# btn7960_board.net
KiCad netlist of a schematic drawn in Altium Designer
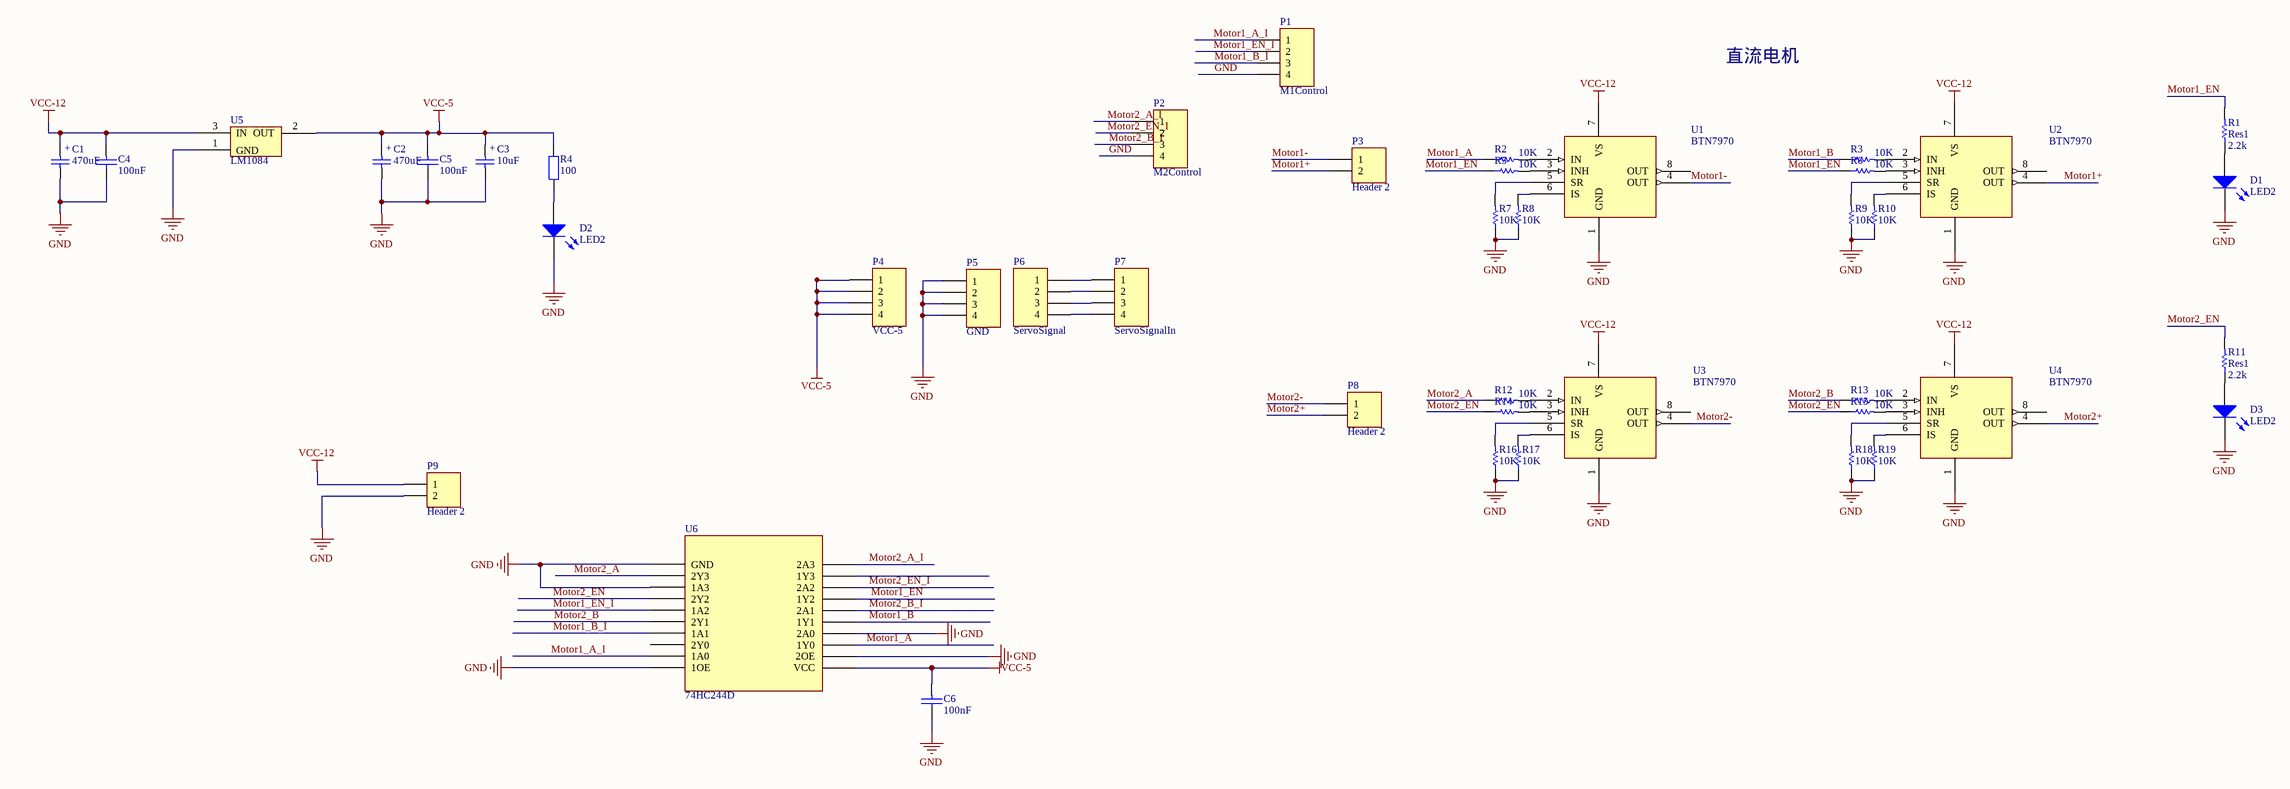
[diagram p0: btn7960_board.SchDoc]

(export (version "E")
  (design (tool "Eeschema 10.0.6"))
  (components
    (comp (ref "C1")
      (value "470uF")
      (footprint "CAP-7343")
      (description "贴片极性电容")
      (fields (field (name "Comment") "Cap"))
      (libsource (lib "SkyWorks2") (part "Cap Pol S"))
    )
    (comp (ref "C2")
      (value "470uF")
      (footprint "CAP-7343")
      (description "贴片极性电容")
      (fields (field (name "Comment") "Cap"))
      (libsource (lib "SkyWorks2") (part "Cap Pol S"))
    )
    (comp (ref "C3")
      (value "10uF")
      (footprint "CAP-7343")
      (description "贴片极性电容")
      (fields (field (name "Comment") "Cap"))
      (libsource (lib "SkyWorks2") (part "Cap Pol S"))
    )
    (comp (ref "C4")
      (value "100nF")
      (footprint "CAP-0603")
      (description "贴片无极性电容")
      (fields (field (name "Comment") "cap smd"))
      (libsource (lib "SkyWorks2") (part "CAP"))
    )
    (comp (ref "C5")
      (value "100nF")
      (footprint "CAP-0603")
      (description "贴片无极性电容")
      (fields (field (name "Comment") "cap smd"))
      (libsource (lib "SkyWorks2") (part "CAP"))
    )
    (comp (ref "C6")
      (value "100nF")
      (footprint "CAP-0603")
      (description "贴片无极性电容")
      (fields (field (name "Comment") "cap smd"))
      (libsource (lib "SkyWorks2") (part "CAP"))
    )
    (comp (ref "D1")
      (value "LED2")
      (footprint "D2012[0805]")
      (description "Typical RED, GREEN, YELLOW, AMBER GaAs LED")
      (fields (field (name "PUBLISHER") "Altium Limited"))
      (libsource (lib "Miscellaneous Devices") (part "LED2"))
    )
    (comp (ref "D2")
      (value "LED2")
      (footprint "D2012[0805]")
      (description "Typical RED, GREEN, YELLOW, AMBER GaAs LED")
      (fields (field (name "PUBLISHER") "Altium Limited"))
      (libsource (lib "SkyWorks2") (part "LED2"))
    )
    (comp (ref "D3")
      (value "LED2")
      (footprint "D2012[0805]")
      (description "Typical RED, GREEN, YELLOW, AMBER GaAs LED")
      (fields (field (name "PUBLISHER") "Altium Limited"))
      (libsource (lib "Miscellaneous Devices") (part "LED2"))
    )
    (comp (ref "P1")
      (value "M1Control")
      (footprint "HDR1X4")
      (description "Header, 4-Pin")
      (fields (field (name "PUBLISHER") "Altium Limited"))
      (libsource (lib "Miscellaneous Connectors") (part "Header 4"))
    )
    (comp (ref "P2")
      (value "M2Control")
      (footprint "HDR1X4")
      (description "Header, 4-Pin")
      (fields (field (name "PUBLISHER") "Altium Limited"))
      (libsource (lib "Miscellaneous Connectors") (part "Header 4"))
    )
    (comp (ref "P3")
      (value "Header 2")
      (footprint "WJ500V-5.08-2P")
      (description "Header, 2-Pin")
      (fields (field (name "PUBLISHER") "Altium Limited"))
      (libsource (lib "Miscellaneous Connectors") (part "Header 2"))
    )
    (comp (ref "P4")
      (value "VCC-5")
      (footprint "HDR1X4")
      (description "Header, 4-Pin")
      (fields (field (name "PUBLISHER") "Altium Limited"))
      (libsource (lib "Miscellaneous Connectors") (part "Header 4"))
    )
    (comp (ref "P5")
      (value "GND")
      (footprint "HDR1X4")
      (description "Header, 4-Pin")
      (fields (field (name "PUBLISHER") "Altium Limited"))
      (libsource (lib "Miscellaneous Connectors") (part "Header 4"))
    )
    (comp (ref "P6")
      (value "ServoSignal")
      (footprint "HDR1X4")
      (description "Header, 4-Pin")
      (fields (field (name "PUBLISHER") "Altium Limited"))
      (libsource (lib "") (part "Header 4_1"))
    )
    (comp (ref "P7")
      (value "ServoSignalIn")
      (footprint "HDR1X4")
      (description "Header, 4-Pin")
      (fields (field (name "PUBLISHER") "Altium Limited"))
      (libsource (lib "Miscellaneous Connectors") (part "Header 4"))
    )
    (comp (ref "P8")
      (value "Header 2")
      (footprint "WJ500V-5.08-2P")
      (description "Header, 2-Pin")
      (fields (field (name "PUBLISHER") "Altium Limited"))
      (libsource (lib "Miscellaneous Connectors") (part "Header 2"))
    )
    (comp (ref "P9")
      (value "Header 2")
      (footprint "WJ500V-5.08-2P")
      (description "Header, 2-Pin")
      (fields (field (name "PUBLISHER") "Altium Limited"))
      (libsource (lib "Miscellaneous Connectors") (part "Header 2"))
    )
    (comp (ref "R1")
      (value "Res1")
      (footprint "RES-0603")
      (description "Resistor")
      (fields (field (name "ALTIUM_VALUE") "2.2k") (field (name "PUBLISHER") "Altium Limited"))
      (libsource (lib "Miscellaneous Devices") (part "Res1"))
    )
    (comp (ref "R2")
      (value "10K")
      (footprint "RES-0603")
      (description "Resistor")
      (libsource (lib "MCU") (part "res1"))
    )
    (comp (ref "R3")
      (value "10K")
      (footprint "RES-0603")
      (description "Resistor")
      (libsource (lib "MCU") (part "res1"))
    )
    (comp (ref "R4")
      (value "100")
      (footprint "RES-0603")
      (fields (field (name "Comment") "RES1"))
      (libsource (lib "SkyWorks2") (part "RES1"))
    )
    (comp (ref "R5")
      (value "10K")
      (footprint "RES-0603")
      (description "Resistor")
      (libsource (lib "MCU") (part "res1"))
    )
    (comp (ref "R6")
      (value "10K")
      (footprint "RES-0603")
      (description "Resistor")
      (libsource (lib "MCU") (part "res1"))
    )
    (comp (ref "R7")
      (value "10K")
      (footprint "RES-0603")
      (description "Resistor")
      (libsource (lib "MCU") (part "res1"))
    )
    (comp (ref "R8")
      (value "10K")
      (footprint "RES-0603")
      (description "Resistor")
      (libsource (lib "MCU") (part "res1"))
    )
    (comp (ref "R9")
      (value "10K")
      (footprint "RES-0603")
      (description "Resistor")
      (libsource (lib "MCU") (part "res1"))
    )
    (comp (ref "R10")
      (value "10K")
      (footprint "RES-0603")
      (description "Resistor")
      (libsource (lib "MCU") (part "res1"))
    )
    (comp (ref "R11")
      (value "Res1")
      (footprint "RES-0603")
      (description "Resistor")
      (fields (field (name "ALTIUM_VALUE") "2.2k") (field (name "PUBLISHER") "Altium Limited"))
      (libsource (lib "Miscellaneous Devices") (part "Res1"))
    )
    (comp (ref "R12")
      (value "10K")
      (footprint "RES-0603")
      (description "Resistor")
      (libsource (lib "MCU") (part "res1"))
    )
    (comp (ref "R13")
      (value "10K")
      (footprint "RES-0603")
      (description "Resistor")
      (libsource (lib "MCU") (part "res1"))
    )
    (comp (ref "R14")
      (value "10K")
      (footprint "RES-0603")
      (description "Resistor")
      (libsource (lib "MCU") (part "res1"))
    )
    (comp (ref "R15")
      (value "10K")
      (footprint "RES-0603")
      (description "Resistor")
      (libsource (lib "MCU") (part "res1"))
    )
    (comp (ref "R16")
      (value "10K")
      (footprint "RES-0603")
      (description "Resistor")
      (libsource (lib "MCU") (part "res1"))
    )
    (comp (ref "R17")
      (value "10K")
      (footprint "RES-0603")
      (description "Resistor")
      (libsource (lib "MCU") (part "res1"))
    )
    (comp (ref "R18")
      (value "10K")
      (footprint "RES-0603")
      (description "Resistor")
      (libsource (lib "MCU") (part "res1"))
    )
    (comp (ref "R19")
      (value "10K")
      (footprint "RES-0603")
      (description "Resistor")
      (libsource (lib "MCU") (part "res1"))
    )
    (comp (ref "U1") (value "BTN7970") (footprint "BTN7970") (libsource (lib "transhcan") (part "BTN7970")))
    (comp (ref "U2") (value "BTN7970") (footprint "BTN7970") (libsource (lib "transhcan") (part "BTN7970")))
    (comp (ref "U3") (value "BTN7970") (footprint "BTN7970") (libsource (lib "transhcan") (part "BTN7970")))
    (comp (ref "U4") (value "BTN7970") (footprint "BTN7970") (libsource (lib "transhcan") (part "BTN7970")))
    (comp (ref "U5")
      (value "LM1084")
      (footprint "LC-TO-220(TO-220-3)")
      (libsource (lib "MLI") (part "LM1084"))
    )
    (comp (ref "U6")
      (value "74HC244D")
      (footprint "LC-SOIC-20_300mil")
      (libsource (lib "MLI") (part "74HC244D"))
    )
  )
  (nets
    (net (code "1") (name "/Motor1+") (class "Default")
      (node (ref "P3") (pin "2") (pinfunction "2_2") (pintype "passive"))
      (node (ref "U2") (pin "4") (pinfunction "OUT_4") (pintype "output"))
    )
    (net (code "2") (name "/Motor1-") (class "Default")
      (node (ref "P3") (pin "1") (pinfunction "1_1") (pintype "passive"))
      (node (ref "U1") (pin "4") (pinfunction "OUT_4") (pintype "output"))
    )
    (net (code "3") (name "/Motor1_A") (class "Default")
      (node (ref "R2") (pin "1") (pinfunction "1_1") (pintype "passive"))
      (node (ref "U6") (pin "18") (pinfunction "1Y0_18") (pintype "passive"))
    )
    (net (code "4") (name "/Motor1_A_I") (class "Default")
      (node (ref "P1") (pin "1") (pinfunction "1_1") (pintype "passive"))
      (node (ref "U6") (pin "2") (pinfunction "1A0_2") (pintype "passive"))
    )
    (net (code "5") (name "/Motor1_B") (class "Default")
      (node (ref "R3") (pin "1") (pinfunction "1_1") (pintype "passive"))
      (node (ref "U6") (pin "16") (pinfunction "1Y1_16") (pintype "passive"))
    )
    (net (code "6") (name "/Motor1_B_I") (class "Default")
      (node (ref "P1") (pin "3") (pinfunction "3_3") (pintype "passive"))
      (node (ref "U6") (pin "4") (pinfunction "1A1_4") (pintype "passive"))
    )
    (net (code "7") (name "/Motor1_EN") (class "Default")
      (node (ref "R1") (pin "2") (pinfunction "2_2") (pintype "passive"))
      (node (ref "R5") (pin "1") (pinfunction "1_1") (pintype "passive"))
      (node (ref "R6") (pin "1") (pinfunction "1_1") (pintype "passive"))
      (node (ref "U6") (pin "14") (pinfunction "1Y2_14") (pintype "passive"))
    )
    (net (code "8") (name "/Motor1_EN_I") (class "Default")
      (node (ref "P1") (pin "2") (pinfunction "2_2") (pintype "passive"))
      (node (ref "U6") (pin "6") (pinfunction "1A2_6") (pintype "passive"))
    )
    (net (code "9") (name "/Motor2+") (class "Default")
      (node (ref "P8") (pin "2") (pinfunction "2_2") (pintype "passive"))
      (node (ref "U4") (pin "4") (pinfunction "OUT_4") (pintype "output"))
    )
    (net (code "10") (name "/Motor2-") (class "Default")
      (node (ref "P8") (pin "1") (pinfunction "1_1") (pintype "passive"))
      (node (ref "U3") (pin "4") (pinfunction "OUT_4") (pintype "output"))
    )
    (net (code "11") (name "/Motor2_A") (class "Default")
      (node (ref "R12") (pin "1") (pinfunction "1_1") (pintype "passive"))
      (node (ref "U6") (pin "9") (pinfunction "2Y3_9") (pintype "passive"))
    )
    (net (code "12") (name "/Motor2_A_I") (class "Default")
      (node (ref "P2") (pin "1") (pinfunction "1_1") (pintype "passive"))
      (node (ref "U6") (pin "11") (pinfunction "2A3_11") (pintype "passive"))
    )
    (net (code "13") (name "/Motor2_B") (class "Default")
      (node (ref "R13") (pin "1") (pinfunction "1_1") (pintype "passive"))
      (node (ref "U6") (pin "5") (pinfunction "2Y1_5") (pintype "passive"))
    )
    (net (code "14") (name "/Motor2_B_I") (class "Default")
      (node (ref "P2") (pin "3") (pinfunction "3_3") (pintype "passive"))
      (node (ref "U6") (pin "15") (pinfunction "2A1_15") (pintype "passive"))
    )
    (net (code "15") (name "/Motor2_EN") (class "Default")
      (node (ref "R11") (pin "2") (pinfunction "2_2") (pintype "passive"))
      (node (ref "R14") (pin "1") (pinfunction "1_1") (pintype "passive"))
      (node (ref "R15") (pin "1") (pinfunction "1_1") (pintype "passive"))
      (node (ref "U6") (pin "7") (pinfunction "2Y2_7") (pintype "passive"))
    )
    (net (code "16") (name "/Motor2_EN_I") (class "Default")
      (node (ref "P2") (pin "2") (pinfunction "2_2") (pintype "passive"))
      (node (ref "U6") (pin "13") (pinfunction "2A2_13") (pintype "passive"))
    )
    (net (code "17") (name "GND") (class "Default")
      (node (ref "C1") (pin "2") (pinfunction "-_2") (pintype "passive"))
      (node (ref "C2") (pin "2") (pinfunction "-_2") (pintype "passive"))
      (node (ref "C3") (pin "2") (pinfunction "-_2") (pintype "passive"))
      (node (ref "C4") (pin "2") (pinfunction "2_2") (pintype "passive"))
      (node (ref "C5") (pin "2") (pinfunction "2_2") (pintype "passive"))
      (node (ref "C6") (pin "2") (pinfunction "2_2") (pintype "passive"))
      (node (ref "D1") (pin "2") (pinfunction "K_2") (pintype "passive"))
      (node (ref "D2") (pin "2") (pinfunction "K_2") (pintype "passive"))
      (node (ref "D3") (pin "2") (pinfunction "K_2") (pintype "passive"))
      (node (ref "P1") (pin "4") (pinfunction "4_4") (pintype "passive"))
      (node (ref "P2") (pin "4") (pinfunction "4_4") (pintype "passive"))
      (node (ref "P5") (pin "1") (pinfunction "1_1") (pintype "passive"))
      (node (ref "P5") (pin "2") (pinfunction "2_2") (pintype "passive"))
      (node (ref "P5") (pin "3") (pinfunction "3_3") (pintype "passive"))
      (node (ref "P5") (pin "4") (pinfunction "4_4") (pintype "passive"))
      (node (ref "P9") (pin "2") (pinfunction "2_2") (pintype "passive"))
      (node (ref "R10") (pin "1") (pinfunction "1_1") (pintype "passive"))
      (node (ref "R16") (pin "1") (pinfunction "1_1") (pintype "passive"))
      (node (ref "R17") (pin "1") (pinfunction "1_1") (pintype "passive"))
      (node (ref "R18") (pin "1") (pinfunction "1_1") (pintype "passive"))
      (node (ref "R19") (pin "1") (pinfunction "1_1") (pintype "passive"))
      (node (ref "R7") (pin "1") (pinfunction "1_1") (pintype "passive"))
      (node (ref "R8") (pin "1") (pinfunction "1_1") (pintype "passive"))
      (node (ref "R9") (pin "1") (pinfunction "1_1") (pintype "passive"))
      (node (ref "U1") (pin "1") (pinfunction "GND_1") (pintype "passive"))
      (node (ref "U2") (pin "1") (pinfunction "GND_1") (pintype "passive"))
      (node (ref "U3") (pin "1") (pinfunction "GND_1") (pintype "passive"))
      (node (ref "U4") (pin "1") (pinfunction "GND_1") (pintype "passive"))
      (node (ref "U5") (pin "1") (pinfunction "GND_1") (pintype "passive"))
      (node (ref "U6") (pin "1") (pinfunction "1OE_1") (pintype "passive"))
      (node (ref "U6") (pin "10") (pinfunction "GND_10") (pintype "passive"))
      (node (ref "U6") (pin "17") (pinfunction "2A0_17") (pintype "passive"))
      (node (ref "U6") (pin "19") (pinfunction "2OE_19") (pintype "passive"))
      (node (ref "U6") (pin "8") (pinfunction "1A3_8") (pintype "passive"))
    )
    (net (code "18") (name "Net-(D1-A)") (class "Default")
      (node (ref "D1") (pin "1") (pinfunction "A_1") (pintype "passive"))
      (node (ref "R1") (pin "1") (pinfunction "1_1") (pintype "passive"))
    )
    (net (code "19") (name "Net-(D2-A)") (class "Default")
      (node (ref "D2") (pin "1") (pinfunction "A_1") (pintype "passive"))
      (node (ref "R4") (pin "1") (pinfunction "1_1") (pintype "passive"))
    )
    (net (code "20") (name "Net-(D3-A)") (class "Default")
      (node (ref "D3") (pin "1") (pinfunction "A_1") (pintype "passive"))
      (node (ref "R11") (pin "1") (pinfunction "1_1") (pintype "passive"))
    )
    (net (code "21") (name "Net-(P6-Pad1)") (class "Default")
      (node (ref "P6") (pin "1") (pinfunction "1_1") (pintype "passive"))
      (node (ref "P7") (pin "1") (pinfunction "1_1") (pintype "passive"))
    )
    (net (code "22") (name "Net-(P6-Pad2)") (class "Default")
      (node (ref "P6") (pin "2") (pinfunction "2_2") (pintype "passive"))
      (node (ref "P7") (pin "2") (pinfunction "2_2") (pintype "passive"))
    )
    (net (code "23") (name "Net-(P6-Pad3)") (class "Default")
      (node (ref "P6") (pin "3") (pinfunction "3_3") (pintype "passive"))
      (node (ref "P7") (pin "3") (pinfunction "3_3") (pintype "passive"))
    )
    (net (code "24") (name "Net-(P6-Pad4)") (class "Default")
      (node (ref "P6") (pin "4") (pinfunction "4_4") (pintype "passive"))
      (node (ref "P7") (pin "4") (pinfunction "4_4") (pintype "passive"))
    )
    (net (code "25") (name "Net-(U1-IN)") (class "Default")
      (node (ref "R2") (pin "2") (pinfunction "2_2") (pintype "passive"))
      (node (ref "U1") (pin "2") (pinfunction "IN_2") (pintype "input"))
    )
    (net (code "26") (name "Net-(U1-INH)") (class "Default")
      (node (ref "R5") (pin "2") (pinfunction "2_2") (pintype "passive"))
      (node (ref "U1") (pin "3") (pinfunction "INH_3") (pintype "input"))
    )
    (net (code "27") (name "Net-(U1-IS)") (class "Default")
      (node (ref "R8") (pin "2") (pinfunction "2_2") (pintype "passive"))
      (node (ref "U1") (pin "6") (pinfunction "IS_6") (pintype "passive"))
    )
    (net (code "28") (name "Net-(U1-SR)") (class "Default")
      (node (ref "R7") (pin "2") (pinfunction "2_2") (pintype "passive"))
      (node (ref "U1") (pin "5") (pinfunction "SR_5") (pintype "passive"))
    )
    (net (code "29") (name "Net-(U2-IN)") (class "Default")
      (node (ref "R3") (pin "2") (pinfunction "2_2") (pintype "passive"))
      (node (ref "U2") (pin "2") (pinfunction "IN_2") (pintype "input"))
    )
    (net (code "30") (name "Net-(U2-INH)") (class "Default")
      (node (ref "R6") (pin "2") (pinfunction "2_2") (pintype "passive"))
      (node (ref "U2") (pin "3") (pinfunction "INH_3") (pintype "input"))
    )
    (net (code "31") (name "Net-(U2-IS)") (class "Default")
      (node (ref "R10") (pin "2") (pinfunction "2_2") (pintype "passive"))
      (node (ref "U2") (pin "6") (pinfunction "IS_6") (pintype "passive"))
    )
    (net (code "32") (name "Net-(U2-SR)") (class "Default")
      (node (ref "R9") (pin "2") (pinfunction "2_2") (pintype "passive"))
      (node (ref "U2") (pin "5") (pinfunction "SR_5") (pintype "passive"))
    )
    (net (code "33") (name "Net-(U3-IN)") (class "Default")
      (node (ref "R12") (pin "2") (pinfunction "2_2") (pintype "passive"))
      (node (ref "U3") (pin "2") (pinfunction "IN_2") (pintype "input"))
    )
    (net (code "34") (name "Net-(U3-INH)") (class "Default")
      (node (ref "R14") (pin "2") (pinfunction "2_2") (pintype "passive"))
      (node (ref "U3") (pin "3") (pinfunction "INH_3") (pintype "input"))
    )
    (net (code "35") (name "Net-(U3-IS)") (class "Default")
      (node (ref "R17") (pin "2") (pinfunction "2_2") (pintype "passive"))
      (node (ref "U3") (pin "6") (pinfunction "IS_6") (pintype "passive"))
    )
    (net (code "36") (name "Net-(U3-SR)") (class "Default")
      (node (ref "R16") (pin "2") (pinfunction "2_2") (pintype "passive"))
      (node (ref "U3") (pin "5") (pinfunction "SR_5") (pintype "passive"))
    )
    (net (code "37") (name "Net-(U4-IN)") (class "Default")
      (node (ref "R13") (pin "2") (pinfunction "2_2") (pintype "passive"))
      (node (ref "U4") (pin "2") (pinfunction "IN_2") (pintype "input"))
    )
    (net (code "38") (name "Net-(U4-INH)") (class "Default")
      (node (ref "R15") (pin "2") (pinfunction "2_2") (pintype "passive"))
      (node (ref "U4") (pin "3") (pinfunction "INH_3") (pintype "input"))
    )
    (net (code "39") (name "Net-(U4-IS)") (class "Default")
      (node (ref "R19") (pin "2") (pinfunction "2_2") (pintype "passive"))
      (node (ref "U4") (pin "6") (pinfunction "IS_6") (pintype "passive"))
    )
    (net (code "40") (name "Net-(U4-SR)") (class "Default")
      (node (ref "R18") (pin "2") (pinfunction "2_2") (pintype "passive"))
      (node (ref "U4") (pin "5") (pinfunction "SR_5") (pintype "passive"))
    )
    (net (code "41") (name "VCC-5") (class "Default")
      (node (ref "C2") (pin "1") (pinfunction "+_1") (pintype "passive"))
      (node (ref "C3") (pin "1") (pinfunction "+_1") (pintype "passive"))
      (node (ref "C5") (pin "1") (pinfunction "1_1") (pintype "passive"))
      (node (ref "C6") (pin "1") (pinfunction "1_1") (pintype "passive"))
      (node (ref "P4") (pin "1") (pinfunction "1_1") (pintype "passive"))
      (node (ref "P4") (pin "2") (pinfunction "2_2") (pintype "passive"))
      (node (ref "P4") (pin "3") (pinfunction "3_3") (pintype "passive"))
      (node (ref "P4") (pin "4") (pinfunction "4_4") (pintype "passive"))
      (node (ref "R4") (pin "2") (pinfunction "2_2") (pintype "passive"))
      (node (ref "U5") (pin "2") (pinfunction "OUT_2") (pintype "passive"))
      (node (ref "U6") (pin "20") (pinfunction "VCC_20") (pintype "passive"))
    )
    (net (code "42") (name "VCC-12") (class "Default")
      (node (ref "C1") (pin "1") (pinfunction "+_1") (pintype "passive"))
      (node (ref "C4") (pin "1") (pinfunction "1_1") (pintype "passive"))
      (node (ref "P9") (pin "1") (pinfunction "1_1") (pintype "passive"))
      (node (ref "U1") (pin "7") (pinfunction "VS_7") (pintype "passive"))
      (node (ref "U2") (pin "7") (pinfunction "VS_7") (pintype "passive"))
      (node (ref "U3") (pin "7") (pinfunction "VS_7") (pintype "passive"))
      (node (ref "U4") (pin "7") (pinfunction "VS_7") (pintype "passive"))
      (node (ref "U5") (pin "3") (pinfunction "IN_3") (pintype "passive"))
    )
    (net (code "43") (name "unconnected-(U1-OUT-Pad8)") (class "Default")
      (node (ref "U1") (pin "8") (pinfunction "OUT_8") (pintype "output"))
    )
    (net (code "44") (name "unconnected-(U2-OUT-Pad8)") (class "Default")
      (node (ref "U2") (pin "8") (pinfunction "OUT_8") (pintype "output"))
    )
    (net (code "45") (name "unconnected-(U3-OUT-Pad8)") (class "Default")
      (node (ref "U3") (pin "8") (pinfunction "OUT_8") (pintype "output"))
    )
    (net (code "46") (name "unconnected-(U4-OUT-Pad8)") (class "Default")
      (node (ref "U4") (pin "8") (pinfunction "OUT_8") (pintype "output"))
    )
    (net (code "47") (name "unconnected-(U6-1Y3-Pad12)") (class "Default")
      (node (ref "U6") (pin "12") (pinfunction "1Y3_12") (pintype "passive"))
    )
    (net (code "48") (name "unconnected-(U6-2Y0-Pad3)") (class "Default")
      (node (ref "U6") (pin "3") (pinfunction "2Y0_3") (pintype "passive"))
    )
  )
)
